# wireless_attachment.net
KiCad netlist of a schematic drawn in EAGLE
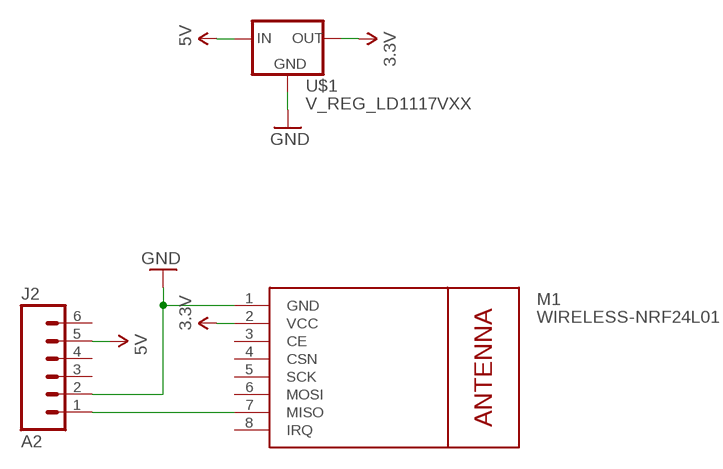
[diagram p0: schematic, sheet 1]

(export (version "E")
  (design (tool "Eeschema 10.0.6"))
  (components
    (comp (ref "J2")
      (value "A2")
      (footprint "eagle-import:BTA")
      (libsource (lib "eagle-import") (part "M06VERNIER-ANALOG"))
    )
    (comp (ref "M1")
      (value "WIRELESS-NRF24L01")
      (footprint "eagle-import:WIRELESS-NRF24L01")
      (libsource (lib "eagle-import") (part "WIRELESS-NRF24L01"))
    )
    (comp (ref "U$1")
      (value "V_REG_LD1117VXX")
      (footprint "eagle-import:78XXL")
      (libsource (lib "eagle-import") (part "V_REG_LD1117VXX"))
    )
  )
  (nets
    (net (code "1") (name "3.3V") (class "Default")
      (node (ref "M1") (pin "2") (pinfunction "VCC_2") (pintype "power_in"))
      (node (ref "U$1") (pin "GND") (pinfunction "OUT_GND") (pintype "passive"))
    )
    (net (code "2") (name "5V") (class "Default")
      (node (ref "J2") (pin "5") (pinfunction "5_5") (pintype "passive"))
      (node (ref "U$1") (pin "OUT") (pinfunction "IN_OUT") (pintype "input"))
    )
    (net (code "3") (name "GND") (class "Default")
      (node (ref "J2") (pin "2") (pinfunction "2_2") (pintype "passive"))
      (node (ref "M1") (pin "1") (pinfunction "GND_1") (pintype "power_in"))
      (node (ref "U$1") (pin "IN") (pinfunction "GND_IN") (pintype "input"))
    )
    (net (code "4") (name "Net-(M1-MISO)") (class "Default")
      (node (ref "J2") (pin "1") (pinfunction "1_1") (pintype "passive"))
      (node (ref "M1") (pin "7") (pinfunction "MISO_7") (pintype "bidirectional"))
    )
    (net (code "5") (name "unconnected-(J2-Pad3)") (class "Default")
      (node (ref "J2") (pin "3") (pinfunction "3_3") (pintype "passive"))
    )
    (net (code "6") (name "unconnected-(J2-Pad4)") (class "Default")
      (node (ref "J2") (pin "4") (pinfunction "4_4") (pintype "passive"))
    )
    (net (code "7") (name "unconnected-(J2-Pad6)") (class "Default")
      (node (ref "J2") (pin "6") (pinfunction "6_6") (pintype "passive"))
    )
    (net (code "8") (name "unconnected-(M1-CE-Pad3)") (class "Default")
      (node (ref "M1") (pin "3") (pinfunction "CE_3") (pintype "bidirectional"))
    )
    (net (code "9") (name "unconnected-(M1-CSN-Pad4)") (class "Default")
      (node (ref "M1") (pin "4") (pinfunction "CSN_4") (pintype "bidirectional"))
    )
    (net (code "10") (name "unconnected-(M1-IRQ-Pad8)") (class "Default")
      (node (ref "M1") (pin "8") (pinfunction "IRQ_8") (pintype "bidirectional"))
    )
    (net (code "11") (name "unconnected-(M1-MOSI-Pad6)") (class "Default")
      (node (ref "M1") (pin "6") (pinfunction "MOSI_6") (pintype "bidirectional"))
    )
    (net (code "12") (name "unconnected-(M1-SCK-Pad5)") (class "Default")
      (node (ref "M1") (pin "5") (pinfunction "SCK_5") (pintype "bidirectional"))
    )
  )
)
